# pca20020_sheet4_pin_map.net
KiCad netlist of a schematic drawn in Altium Designer
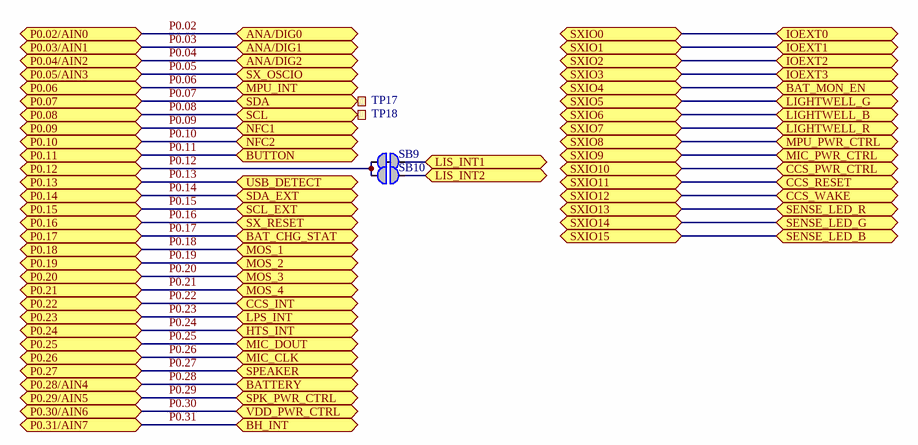
[diagram p0: pca20020_sheet4_pin_map.SchDoc]

(export (version "E")
  (design (tool "Eeschema 10.0.6"))
  (components
    (comp (ref "SB9")
      (value "Solderbridge")
      (footprint "Solderbridge_Shorted")
      (description "Shorted Solderbridge")
      (fields
        (field (name "PART NUMBER") "Solderbridge Shorted")
        (field (name "PUBLISHER") "Nordic Semiconductor")
      )
      (libsource (lib "Nordic Passive DB") (part "SOLDERBRIDGE_SHORTED"))
    )
    (comp (ref "SB10")
      (value "Solderbridge")
      (footprint "Solderbridge")
      (fields (field (name "PUBLISHER") "Nordic Semiconductor"))
      (libsource (lib "Nordic Passive DB") (part "SOLDERBRIDGE"))
    )
    (comp (ref "TP17")
      (value "Ø1.5mm,SMD")
      (footprint "TP_SMD_Ø1.5mm")
      (description "1.0mm circular SMD testpad")
      (fields
        (field (name "PART NUMBER") "TP_SMD_Ø1.5MM")
        (field (name "MANUFACTURER") "Nordic Semiconductor")
        (field (name "PUBLISHER") "Nordic Semiconductor")
      )
      (libsource (lib "Nordic Passive DB") (part "TESTPAD"))
    )
    (comp (ref "TP18")
      (value "Ø1.5mm,SMD")
      (footprint "TP_SMD_Ø1.5mm")
      (description "1.0mm circular SMD testpad")
      (fields
        (field (name "PART NUMBER") "TP_SMD_Ø1.5MM")
        (field (name "MANUFACTURER") "Nordic Semiconductor")
        (field (name "PUBLISHER") "Nordic Semiconductor")
      )
      (libsource (lib "Nordic Passive DB") (part "TESTPAD"))
    )
  )
  (nets
    (net (code "12") (name "/LIS_INT1") (class "Default")
      (node (ref "SB9") (pin "1") (pinfunction "0_1") (pintype "passive"))
    )
    (net (code "13") (name "/LIS_INT2") (class "Default")
      (node (ref "SB10") (pin "1") (pinfunction "0_1") (pintype "passive"))
    )
    (net (code "21") (name "/P0.07") (class "Default")
      (node (ref "TP17") (pin "1") (pinfunction "1_1") (pintype "passive"))
    )
    (net (code "22") (name "/P0.08") (class "Default")
      (node (ref "TP18") (pin "1") (pinfunction "1_1") (pintype "passive"))
    )
    (net (code "26") (name "/P0.12") (class "Default")
      (node (ref "SB10") (pin "2") (pinfunction "1_2") (pintype "passive"))
      (node (ref "SB9") (pin "2") (pinfunction "1_2") (pintype "passive"))
    )
  )
)
